# SolenoidWiring.net
KiCad netlist of a schematic drawn in EAGLE
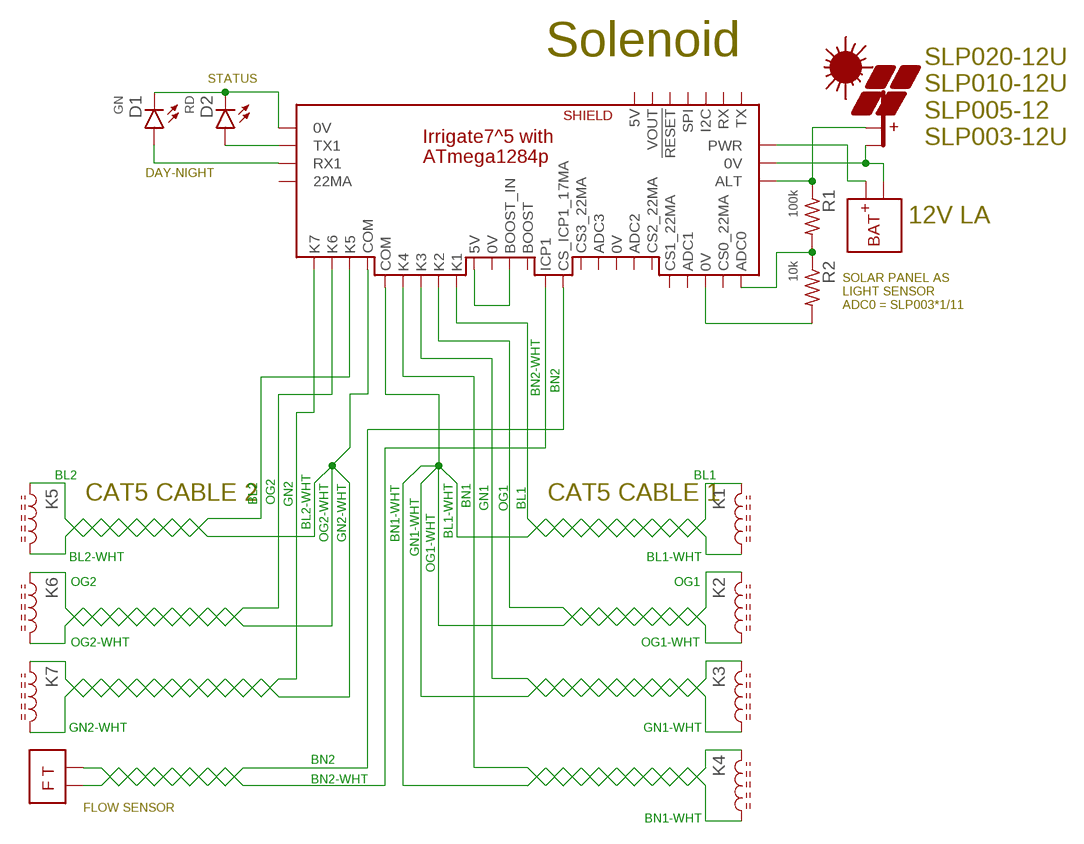
[diagram p0: schematic, sheet 1]

(export (version "E")
  (design (tool "Eeschema 10.0.6"))
  (components
    (comp (ref "D1")
      (value "GN")
      (footprint "eagle-import:LED5MM")
      (libsource (lib "eagle-import") (part "LED5MM"))
    )
    (comp (ref "D2")
      (value "RD")
      (footprint "eagle-import:LED5MM")
      (libsource (lib "eagle-import") (part "LED5MM"))
    )
    (comp (ref "K1")
      (value "L0805")
      (footprint "eagle-import:C0805(2012)")
      (libsource (lib "eagle-import") (part "L0805"))
    )
    (comp (ref "K2")
      (value "L0805")
      (footprint "eagle-import:C0805(2012)")
      (libsource (lib "eagle-import") (part "L0805"))
    )
    (comp (ref "K3")
      (value "L0805")
      (footprint "eagle-import:C0805(2012)")
      (libsource (lib "eagle-import") (part "L0805"))
    )
    (comp (ref "K4")
      (value "L0805")
      (footprint "eagle-import:C0805(2012)")
      (libsource (lib "eagle-import") (part "L0805"))
    )
    (comp (ref "K5")
      (value "L0805")
      (footprint "eagle-import:C0805(2012)")
      (libsource (lib "eagle-import") (part "L0805"))
    )
    (comp (ref "K6")
      (value "L0805")
      (footprint "eagle-import:C0805(2012)")
      (libsource (lib "eagle-import") (part "L0805"))
    )
    (comp (ref "K7")
      (value "L0805")
      (footprint "eagle-import:C0805(2012)")
      (libsource (lib "eagle-import") (part "L0805"))
    )
    (comp (ref "PV4")
      (value "PV")
      (footprint "eagle-import:NA-30")
      (libsource (lib "eagle-import") (part "PV"))
    )
    (comp (ref "R1")
      (value "100k")
      (footprint "eagle-import:C0805(2012)")
      (libsource (lib "eagle-import") (part "R0805"))
    )
    (comp (ref "R2")
      (value "10k")
      (footprint "eagle-import:C0805(2012)")
      (libsource (lib "eagle-import") (part "R0805"))
    )
    (comp (ref "U$1")
      (value "IRRIGATE7")
      (footprint "eagle-import:WITH_RPU_NAMES")
      (libsource (lib "eagle-import") (part "IRRIGATE7"))
    )
    (comp (ref "U$3")
      (value "FT")
      (footprint "eagle-import:NA-30")
      (libsource (lib "eagle-import") (part "FT"))
    )
    (comp (ref "U$7")
      (value "BAT")
      (footprint "eagle-import:NA-30")
      (libsource (lib "eagle-import") (part "BAT"))
    )
  )
  (nets
    (net (code "1") (name "/BL1") (class "Default")
      (node (ref "K1") (pin "1") (pinfunction "1_1") (pintype "passive"))
      (node (ref "U$1") (pin "K1") (pinfunction "K1_K1") (pintype "bidirectional"))
    )
    (net (code "2") (name "/BL1-WHT") (class "Default")
      (node (ref "K1") (pin "2") (pinfunction "2_2") (pintype "passive"))
    )
    (net (code "3") (name "/BL2") (class "Default")
      (node (ref "K5") (pin "1") (pinfunction "1_1") (pintype "passive"))
      (node (ref "U$1") (pin "K5") (pinfunction "K5_K5") (pintype "bidirectional"))
    )
    (net (code "4") (name "/BL2-WHT") (class "Default")
      (node (ref "K5") (pin "2") (pinfunction "2_2") (pintype "passive"))
    )
    (net (code "5") (name "/BN1") (class "Default")
      (node (ref "K4") (pin "1") (pinfunction "1_1") (pintype "passive"))
      (node (ref "U$1") (pin "K4") (pinfunction "K4_K4") (pintype "bidirectional"))
    )
    (net (code "6") (name "/BN1-WHT") (class "Default")
      (node (ref "K4") (pin "2") (pinfunction "2_2") (pintype "passive"))
    )
    (net (code "7") (name "/BN2") (class "Default")
      (node (ref "U$1") (pin "17MA@ICP1") (pinfunction "CS_ICP1_17MA_17MA@ICP1") (pintype "bidirectional"))
      (node (ref "U$3") (pin "2") (pinfunction "PWR_2") (pintype "bidirectional"))
    )
    (net (code "8") (name "/BN2-WHT") (class "Default")
      (node (ref "U$1") (pin "ICP1") (pinfunction "ICP1_ICP1") (pintype "bidirectional"))
      (node (ref "U$3") (pin "1") (pinfunction "PL_1") (pintype "bidirectional"))
    )
    (net (code "9") (name "/GN1") (class "Default")
      (node (ref "K3") (pin "1") (pinfunction "1_1") (pintype "passive"))
      (node (ref "U$1") (pin "K3") (pinfunction "K3_K3") (pintype "bidirectional"))
    )
    (net (code "10") (name "/GN1-WHT") (class "Default")
      (node (ref "K3") (pin "2") (pinfunction "2_2") (pintype "passive"))
    )
    (net (code "11") (name "/GN2") (class "Default")
      (node (ref "K7") (pin "1") (pinfunction "1_1") (pintype "passive"))
      (node (ref "U$1") (pin "K7") (pinfunction "K7_K7") (pintype "bidirectional"))
    )
    (net (code "12") (name "/GN2-WHT") (class "Default")
      (node (ref "K7") (pin "2") (pinfunction "2_2") (pintype "passive"))
    )
    (net (code "13") (name "/OG1") (class "Default")
      (node (ref "K2") (pin "1") (pinfunction "1_1") (pintype "passive"))
      (node (ref "U$1") (pin "K2") (pinfunction "K2_K2") (pintype "bidirectional"))
    )
    (net (code "14") (name "/OG1-WHT") (class "Default")
      (node (ref "K2") (pin "2") (pinfunction "2_2") (pintype "passive"))
    )
    (net (code "15") (name "/OG2") (class "Default")
      (node (ref "K6") (pin "1") (pinfunction "1_1") (pintype "passive"))
      (node (ref "U$1") (pin "K6") (pinfunction "K6_K6") (pintype "bidirectional"))
    )
    (net (code "16") (name "/OG2-WHT") (class "Default")
      (node (ref "K6") (pin "2") (pinfunction "2_2") (pintype "passive"))
    )
    (net (code "17") (name "Net-(D1-PadK)") (class "Default")
      (node (ref "D1") (pin "K") (pinfunction "K_K") (pintype "passive"))
      (node (ref "D2") (pin "K") (pinfunction "K_K") (pintype "passive"))
      (node (ref "U$1") (pin "17MA@ICP3") (pinfunction "0V_17MA@ICP3") (pintype "bidirectional"))
    )
    (net (code "18") (name "Net-(PV4-+PV)") (class "Default")
      (node (ref "PV4") (pin "1") (pinfunction "+PV_1") (pintype "bidirectional"))
      (node (ref "R1") (pin "1") (pinfunction "1_1") (pintype "passive"))
      (node (ref "U$1") (pin "AUX") (pinfunction "ALT_AUX") (pintype "bidirectional"))
    )
    (net (code "19") (name "Net-(PV4--PV)") (class "Default")
      (node (ref "PV4") (pin "2") (pinfunction "-PV_2") (pintype "bidirectional"))
      (node (ref "U$1") (pin "0V@PWR") (pinfunction "0V_0V@PWR") (pintype "bidirectional"))
      (node (ref "U$7") (pin "2") (pinfunction "-BAT_2") (pintype "bidirectional"))
    )
    (net (code "20") (name "Net-(R1-Pad2)") (class "Default")
      (node (ref "R1") (pin "2") (pinfunction "2_2") (pintype "passive"))
      (node (ref "R2") (pin "1") (pinfunction "1_1") (pintype "passive"))
      (node (ref "U$1") (pin "ADC0") (pinfunction "ADC0_ADC0") (pintype "bidirectional"))
    )
    (net (code "21") (name "Net-(R2-Pad2)") (class "Default")
      (node (ref "R2") (pin "2") (pinfunction "2_2") (pintype "passive"))
      (node (ref "U$1") (pin "0V@ADC2") (pinfunction "0V_0V@ADC2") (pintype "bidirectional"))
    )
    (net (code "22") (name "Net-(U$1-Pad5V)") (class "Default")
      (node (ref "U$1") (pin "5V") (pinfunction "5V_5V") (pintype "bidirectional"))
      (node (ref "U$1") (pin "BOOST_IN") (pinfunction "BOOST_IN_BOOST_IN") (pintype "bidirectional"))
    )
    (net (code "23") (name "Net-(U$1-RX1)") (class "Default")
      (node (ref "D1") (pin "A") (pinfunction "A_A") (pintype "passive"))
      (node (ref "U$1") (pin "DIO2") (pinfunction "RX1_DIO2") (pintype "bidirectional"))
    )
    (net (code "24") (name "Net-(U$1-TX1)") (class "Default")
      (node (ref "D2") (pin "A") (pinfunction "A_A") (pintype "passive"))
      (node (ref "U$1") (pin "DIO3") (pinfunction "TX1_DIO3") (pintype "bidirectional"))
    )
    (net (code "25") (name "Net-(U$7-+BAT)") (class "Default")
      (node (ref "U$1") (pin "PWR") (pinfunction "PWR_PWR") (pintype "bidirectional"))
      (node (ref "U$7") (pin "1") (pinfunction "+BAT_1") (pintype "bidirectional"))
    )
    (net (code "26") (name "unconnected-(U$1-0V-PadICP3)") (class "Default")
      (node (ref "U$1") (pin "ICP3") (pinfunction "0V_ICP3") (pintype "bidirectional"))
    )
    (net (code "27") (name "unconnected-(U$1-5V-PadSHLD_5V)") (class "Default")
      (node (ref "U$1") (pin "SHLD_5V") (pinfunction "5V_SHLD_5V") (pintype "bidirectional"))
    )
    (net (code "28") (name "unconnected-(U$1-22MA-Pad22MA@DIO2)") (class "Default")
      (node (ref "U$1") (pin "22MA@DIO2") (pinfunction "22MA_22MA@DIO2") (pintype "bidirectional"))
    )
    (net (code "29") (name "unconnected-(U$1-ADC2-PadADC4)") (class "Default")
      (node (ref "U$1") (pin "ADC4") (pinfunction "ADC2_ADC4") (pintype "bidirectional"))
    )
    (net (code "30") (name "unconnected-(U$1-ADC3-PadADC5)") (class "Default")
      (node (ref "U$1") (pin "ADC5") (pinfunction "ADC3_ADC5") (pintype "bidirectional"))
    )
    (net (code "31") (name "unconnected-(U$1-COM-PadCOM@K4)") (class "Default")
      (node (ref "U$1") (pin "COM@K4") (pinfunction "COM_COM@K4") (pintype "bidirectional"))
    )
    (net (code "32") (name "unconnected-(U$1-COM-PadCOM@K5)") (class "Default")
      (node (ref "U$1") (pin "COM@K5") (pinfunction "COM_COM@K5") (pintype "bidirectional"))
    )
    (net (code "33") (name "unconnected-(U$1-CS0_22MA-Pad22MA@ADC0)") (class "Default")
      (node (ref "U$1") (pin "22MA@ADC0") (pinfunction "CS0_22MA_22MA@ADC0") (pintype "bidirectional"))
    )
    (net (code "34") (name "unconnected-(U$1-CS1_22MA-Pad22MA@ADC1)") (class "Default")
      (node (ref "U$1") (pin "22MA@ADC1") (pinfunction "CS1_22MA_22MA@ADC1") (pintype "bidirectional"))
    )
    (net (code "35") (name "unconnected-(U$1-CS2_22MA-Pad22MA@ADC4)") (class "Default")
      (node (ref "U$1") (pin "22MA@ADC4") (pinfunction "CS2_22MA_22MA@ADC4") (pintype "bidirectional"))
    )
    (net (code "36") (name "unconnected-(U$1-CS3_22MA-Pad22MA@ADC5)") (class "Default")
      (node (ref "U$1") (pin "22MA@ADC5") (pinfunction "CS3_22MA_22MA@ADC5") (pintype "bidirectional"))
    )
    (net (code "37") (name "unconnected-(U$1-Pad0V)") (class "Default")
      (node (ref "U$1") (pin "0V") (pinfunction "0V_0V") (pintype "bidirectional"))
    )
    (net (code "38") (name "unconnected-(U$1-PadADC1)") (class "Default")
      (node (ref "U$1") (pin "ADC1") (pinfunction "ADC1_ADC1") (pintype "bidirectional"))
    )
    (net (code "39") (name "unconnected-(U$1-PadBOOST)") (class "Default")
      (node (ref "U$1") (pin "BOOST") (pinfunction "BOOST_BOOST") (pintype "bidirectional"))
    )
    (net (code "40") (name "unconnected-(U$1-PadI2C)") (class "Default")
      (node (ref "U$1") (pin "I2C") (pinfunction "I2C_I2C") (pintype "bidirectional"))
    )
    (net (code "41") (name "unconnected-(U$1-PadRX)") (class "Default")
      (node (ref "U$1") (pin "RX") (pinfunction "RX_RX") (pintype "bidirectional"))
    )
    (net (code "42") (name "unconnected-(U$1-PadSPI)") (class "Default")
      (node (ref "U$1") (pin "SPI") (pinfunction "SPI_SPI") (pintype "bidirectional"))
    )
    (net (code "43") (name "unconnected-(U$1-PadTX)") (class "Default")
      (node (ref "U$1") (pin "TX") (pinfunction "TX_TX") (pintype "bidirectional"))
    )
    (net (code "44") (name "unconnected-(U$1-VOUT-PadSHLD_VOUT)") (class "Default")
      (node (ref "U$1") (pin "SHLD_VOUT") (pinfunction "VOUT_SHLD_VOUT") (pintype "bidirectional"))
    )
    (net (code "45") (name "unconnected-(U$1-~{RESET}-Pad!RESET)") (class "Default")
      (node (ref "U$1") (pin "!RESET") (pinfunction "~{RESET}_!RESET") (pintype "bidirectional"))
    )
  )
)
